# Sensor_Board.net
KiCad netlist of a schematic drawn in Altium Designer
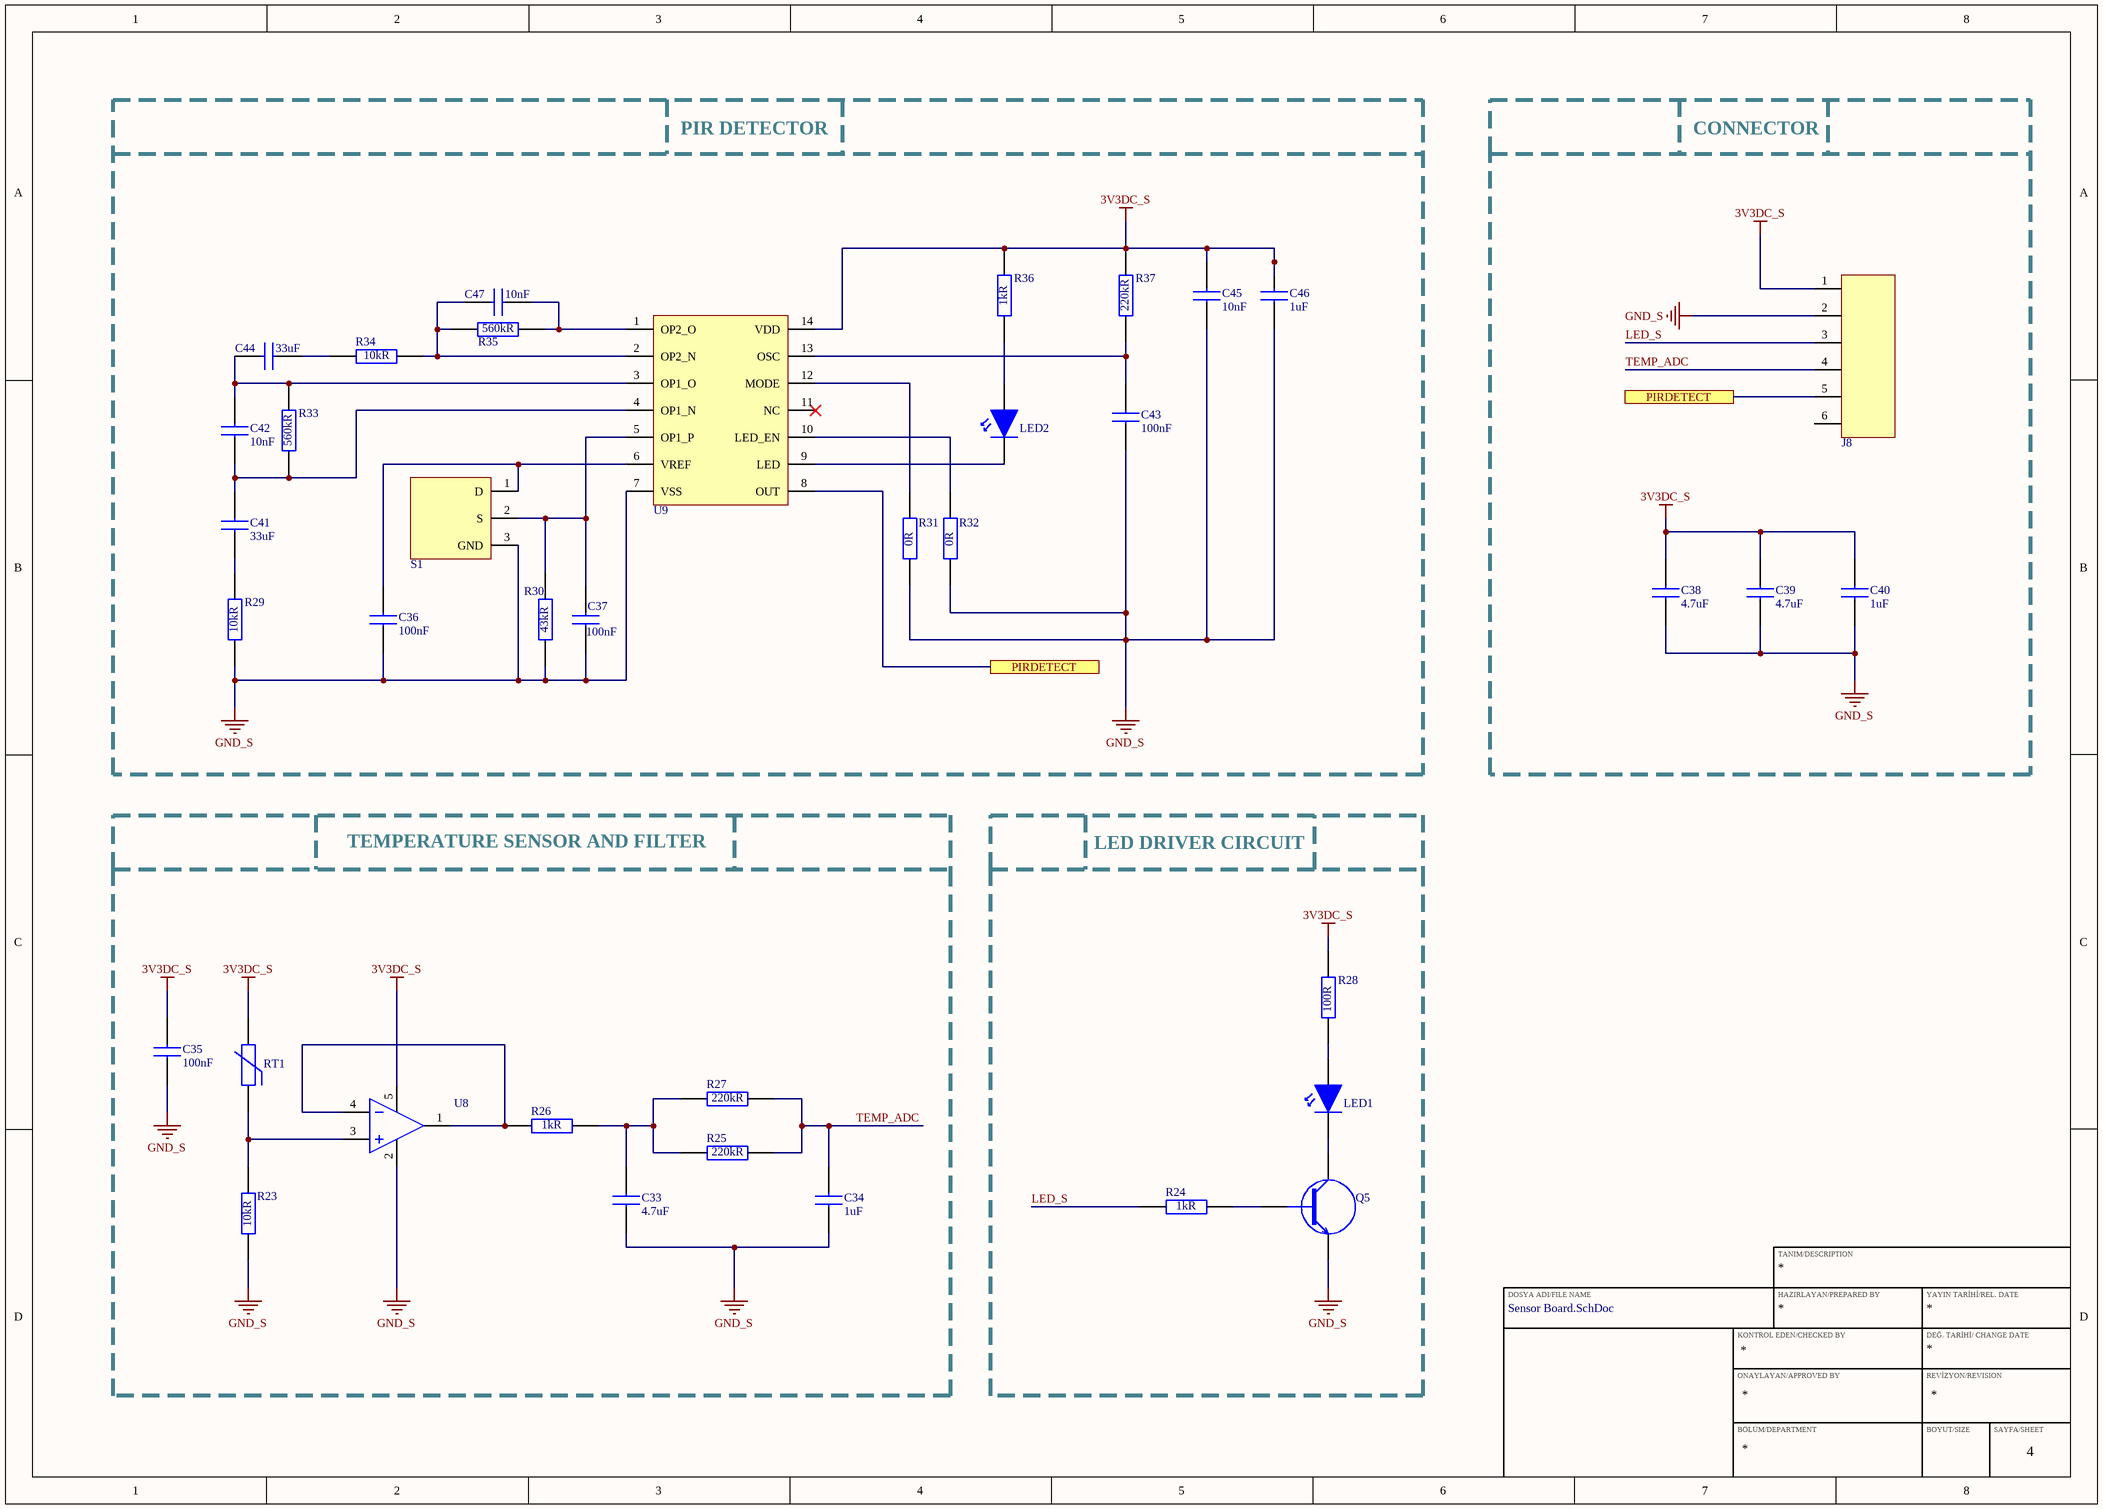
[diagram p0: Sensor Board.SchDoc]

(export (version "E")
  (design (tool "Eeschema 10.0.6"))
  (components
    (comp (ref "C33")
      (value "CL21A475KAQNNNE")
      (footprint "CAP_0805")
      (description "¦CAP CER 4.7UF %10 0805 SMD X5R")
      (fields
        (field (name "MANUFACTURER") "Samsung")
        (field (name "TOLERANCE") "10%")
        (field (name "CAPACITANCE") "4.7uF")
        (field (name "DESIGNED BY") "ADAK")
      )
      (libsource (lib "Udemy_ADAK_Library1") (part "CAP CER 4.7uF 0805"))
    )
    (comp (ref "C34")
      (value "CL21B105KBFNNNE")
      (footprint "CAP_0805")
      (description "¦CAP CER 1UF %10 0805 SMD X7R")
      (fields
        (field (name "MANUFACTURER") "Samsung")
        (field (name "TOLERANCE") "10%")
        (field (name "CAPACITANCE") "1uF")
        (field (name "DESIGNED BY") "ADAK")
      )
      (libsource (lib "Udemy_ADAK_Library1") (part "CAP CER 1uF 0805"))
    )
    (comp (ref "C35")
      (value "C0603C104K4RAC7867")
      (footprint "CAP_0603")
      (description "¦CAP CER 100nF (0.1UF) %10 0603 SMD")
      (fields
        (field (name "MANUFACTURER") "KEMET")
        (field (name "MANUFACTURER PART NUMBER") "C0603C104K4RACTU")
        (field (name "CAPACITANCE") "100nF")
        (field (name "DESIGNED BY") "ADAK")
      )
      (libsource (lib "Udemy_ADAK_Library1") (part "CAP CER 100nF 0603"))
    )
    (comp (ref "C36")
      (value "CL21B104KBCNNNC")
      (footprint "CAP_0805")
      (description "¦CAP CER 0.1UF (100nF) %10 0805 SMD X7R")
      (fields
        (field (name "MANUFACTURER") "Samsung")
        (field (name "TOLERANCE") "10%")
        (field (name "CAPACITANCE") "100nF")
        (field (name "DESIGNED BY") "ADAK")
      )
      (libsource (lib "Udemy_ADAK_Library1") (part "CAP CER 100nF 0805"))
    )
    (comp (ref "C37")
      (value "CL21B104KBCNNNC")
      (footprint "CAP_0805")
      (description "¦CAP CER 0.1UF (100nF) %10 0805 SMD X7R")
      (fields
        (field (name "MANUFACTURER") "Samsung")
        (field (name "TOLERANCE") "10%")
        (field (name "CAPACITANCE") "100nF")
        (field (name "DESIGNED BY") "ADAK")
      )
      (libsource (lib "Udemy_ADAK_Library1") (part "CAP CER 100nF 0805"))
    )
    (comp (ref "C38")
      (value "CL21A475KAQNNNE")
      (footprint "CAP_0805")
      (description "¦CAP CER 4.7UF %10 0805 SMD X5R")
      (fields
        (field (name "MANUFACTURER") "Samsung")
        (field (name "TOLERANCE") "10%")
        (field (name "CAPACITANCE") "4.7uF")
        (field (name "DESIGNED BY") "ADAK")
      )
      (libsource (lib "Udemy_ADAK_Library1") (part "CAP CER 4.7uF 0805"))
    )
    (comp (ref "C39")
      (value "CL21A475KAQNNNE")
      (footprint "CAP_0805")
      (description "¦CAP CER 4.7UF %10 0805 SMD X5R")
      (fields
        (field (name "MANUFACTURER") "Samsung")
        (field (name "TOLERANCE") "10%")
        (field (name "CAPACITANCE") "4.7uF")
        (field (name "DESIGNED BY") "ADAK")
      )
      (libsource (lib "Udemy_ADAK_Library1") (part "CAP CER 4.7uF 0805"))
    )
    (comp (ref "C40")
      (value "CL21B105KBFNNNE")
      (footprint "CAP_0805")
      (description "¦CAP CER 1UF %10 0805 SMD X7R")
      (fields
        (field (name "MANUFACTURER") "Samsung")
        (field (name "TOLERANCE") "10%")
        (field (name "CAPACITANCE") "1uF")
        (field (name "DESIGNED BY") "ADAK")
      )
      (libsource (lib "Udemy_ADAK_Library1") (part "CAP CER 1uF 0805"))
    )
    (comp (ref "C41")
      (value "C2012X5R1A336M125AC")
      (footprint "CAP_0805")
      (description "¦CAP CER 33UF %20 0805 X5R 10V")
      (fields
        (field (name "MANUFACTURER") "TDK")
        (field (name "TOLERANCE") "20%")
        (field (name "CAPACITANCE") "33uF")
        (field (name "DESIGNED BY") "ADAK")
      )
      (libsource (lib "Udemy_ADAK_Library1") (part "CAP CER 33uF 0805"))
    )
    (comp (ref "C42")
      (value "0603B103K160CT")
      (footprint "CAP_0603")
      (description "¦CAP CER 10nF %10 0603 SMD X7R")
      (fields
        (field (name "MANUFACTURER") "Walsin Technologies")
        (field (name "TOLERANCE") "10%")
        (field (name "CAPACITANCE") "10nF")
        (field (name "DESIGNED BY") "ADAK")
      )
      (libsource (lib "Udemy_ADAK_Library1") (part "CAP CER 10nF 0603"))
    )
    (comp (ref "C43")
      (value "CL21B104KBCNNNC")
      (footprint "CAP_0805")
      (description "¦CAP CER 0.1UF (100nF) %10 0805 SMD X7R")
      (fields
        (field (name "MANUFACTURER") "Samsung")
        (field (name "TOLERANCE") "10%")
        (field (name "CAPACITANCE") "100nF")
        (field (name "DESIGNED BY") "ADAK")
      )
      (libsource (lib "Udemy_ADAK_Library1") (part "CAP CER 100nF 0805"))
    )
    (comp (ref "C44")
      (value "C2012X5R1A336M125AC")
      (footprint "CAP_0805")
      (description "¦CAP CER 33UF %20 0805 X5R 10V")
      (fields
        (field (name "MANUFACTURER") "TDK")
        (field (name "TOLERANCE") "20%")
        (field (name "CAPACITANCE") "33uF")
        (field (name "DESIGNED BY") "ADAK")
      )
      (libsource (lib "Udemy_ADAK_Library1") (part "CAP CER 33uF 0805"))
    )
    (comp (ref "C45")
      (value "0603B103K160CT")
      (footprint "CAP_0603")
      (description "¦CAP CER 10nF %10 0603 SMD X7R")
      (fields
        (field (name "MANUFACTURER") "Walsin Technologies")
        (field (name "TOLERANCE") "10%")
        (field (name "CAPACITANCE") "10nF")
        (field (name "DESIGNED BY") "ADAK")
      )
      (libsource (lib "Udemy_ADAK_Library1") (part "CAP CER 10nF 0603"))
    )
    (comp (ref "C46")
      (value "CL21B105KBFNNNE")
      (footprint "CAP_0805")
      (description "¦CAP CER 1UF %10 0805 SMD X7R")
      (fields
        (field (name "MANUFACTURER") "Samsung")
        (field (name "TOLERANCE") "10%")
        (field (name "CAPACITANCE") "1uF")
        (field (name "DESIGNED BY") "ADAK")
      )
      (libsource (lib "Udemy_ADAK_Library1") (part "CAP CER 1uF 0805"))
    )
    (comp (ref "C47")
      (value "0603B103K160CT")
      (footprint "CAP_0603")
      (description "¦CAP CER 10nF %10 0603 SMD X7R")
      (fields
        (field (name "MANUFACTURER") "Walsin Technologies")
        (field (name "TOLERANCE") "10%")
        (field (name "CAPACITANCE") "10nF")
        (field (name "DESIGNED BY") "ADAK")
      )
      (libsource (lib "Udemy_ADAK_Library1") (part "CAP CER 10nF 0603"))
    )
    (comp (ref "J8")
      (value "64800611622")
      (footprint "64800611622")
      (description "¦Connector (1.50mm) 6 Pin Header Through Hole")
      (fields (field (name "MANUFACTURER") "Wurth Electronics") (field (name "DESIGNED BY") "ADAK"))
      (libsource (lib "Udemy_ADAK_Library1") (part "64800611622_CONN_6P"))
    )
    (comp (ref "LED1")
      (value "150080SS75000")
      (footprint "LED_RED_0805")
      (description "¦LED RED CLEAR 0805 SMD")
      (fields (field (name "MANUFACTURER") "Wurth Electronics") (field (name "DESIGNED BY") "ADAK"))
      (libsource (lib "Udemy_ADAK_Library1") (part "LED RED 0805"))
    )
    (comp (ref "LED2")
      (value "150080GS75000")
      (footprint "LED_GREEN_0805")
      (description "¦LED GREEN CLEAR 0805 SMD")
      (fields (field (name "MANUFACTURER") "Wurth Electronics") (field (name "DESIGNED BY") "ADAK"))
      (libsource (lib "Udemy_ADAK_Library1") (part "LED GREEN 0805"))
    )
    (comp (ref "Q5")
      (value "MMBT3904-7-F")
      (footprint "SOT-23F")
      (description "¦Bipolar (BJT) Transistor NPN 40 V 200 mA 300MHz 300 mW Surface Mount SOT-23-3")
      (fields (field (name "MANUFACTURER") "Diodes Zetex") (field (name "DESIGNED BY") "ADAK"))
      (libsource (lib "Udemy_ADAK_Library1") (part "MMBT3904-7-F"))
    )
    (comp (ref "R23")
      (value "RC0603FR-0710KL")
      (footprint "RES_0603")
      (description "¦RES 10KΩ 1% 0603 SMD")
      (fields
        (field (name "MANUFACTURER") "Yageo")
        (field (name "TOLERANCE") "1%")
        (field (name "RESISTANCE") "10kR")
        (field (name "DESIGNED BY") "ADAK")
      )
      (libsource (lib "Udemy_ADAK_Library1") (part "RES 10K OHM 0603"))
    )
    (comp (ref "R24")
      (value "RC0603FR-071KL")
      (footprint "RES_0603")
      (description "¦RES 1KΩ 1% 0603 SMD")
      (fields
        (field (name "MANUFACTURER") "Yageo")
        (field (name "TOLERANCE") "1%")
        (field (name "RESISTANCE") "1kR")
        (field (name "DESIGNED BY") "ADAK")
      )
      (libsource (lib "Udemy_ADAK_Library1") (part "RES 1K OHM 0603"))
    )
    (comp (ref "R25")
      (value "RC0603JR-07220KL")
      (footprint "RES_0603")
      (description "¦RES 220KΩ 5% 0603 SMD")
      (fields
        (field (name "MANUFACTURER") "Yageo")
        (field (name "TOLERANCE") "5%")
        (field (name "RESISTANCE") "220kR")
        (field (name "DESIGNED BY") "ADAK")
      )
      (libsource (lib "Udemy_ADAK_Library1") (part "RES 220K OHM 0603"))
    )
    (comp (ref "R26")
      (value "RC0603FR-071KL")
      (footprint "RES_0603")
      (description "¦RES 1KΩ 1% 0603 SMD")
      (fields
        (field (name "MANUFACTURER") "Yageo")
        (field (name "TOLERANCE") "1%")
        (field (name "RESISTANCE") "1kR")
        (field (name "DESIGNED BY") "ADAK")
      )
      (libsource (lib "Udemy_ADAK_Library1") (part "RES 1K OHM 0603"))
    )
    (comp (ref "R27")
      (value "RC0603JR-07220KL")
      (footprint "RES_0603")
      (description "¦RES 220KΩ 5% 0603 SMD")
      (fields
        (field (name "MANUFACTURER") "Yageo")
        (field (name "TOLERANCE") "5%")
        (field (name "RESISTANCE") "220kR")
        (field (name "DESIGNED BY") "ADAK")
      )
      (libsource (lib "Udemy_ADAK_Library1") (part "RES 220K OHM 0603"))
    )
    (comp (ref "R28")
      (value "RC0603JR-13100RL")
      (footprint "RES_0603")
      (description "¦RES 100Ω 5% 0603 SMD")
      (fields
        (field (name "MANUFACTURER") "Yageo")
        (field (name "TOLERANCE") "5%")
        (field (name "RESISTANCE") "100R")
        (field (name "DESIGNED BY") "ADAK")
      )
      (libsource (lib "Udemy_ADAK_Library1") (part "RES 100 OHM 0603"))
    )
    (comp (ref "R29")
      (value "RC0603FR-0710KL")
      (footprint "RES_0603")
      (description "¦RES 10KΩ 1% 0603 SMD")
      (fields
        (field (name "MANUFACTURER") "Yageo")
        (field (name "TOLERANCE") "1%")
        (field (name "RESISTANCE") "10kR")
        (field (name "DESIGNED BY") "ADAK")
      )
      (libsource (lib "Udemy_ADAK_Library1") (part "RES 10K OHM 0603"))
    )
    (comp (ref "R30")
      (value "RC0603FR-0743KL")
      (footprint "RES_0603")
      (description "¦RES 43KΩ 1% 0603 SMD")
      (fields
        (field (name "MANUFACTURER") "Yageo")
        (field (name "TOLERANCE") "1%")
        (field (name "RESISTANCE") "43kR")
        (field (name "DESIGNED BY") "ADAK")
      )
      (libsource (lib "Udemy_ADAK_Library1") (part "RES 43K OHM 0603"))
    )
    (comp (ref "R31")
      (value "RC0603JR-070RL")
      (footprint "RES_0603")
      (description "¦RES 0Ω 0603 SMD JUMPER")
      (fields
        (field (name "MANUFACTURER") "Yageo")
        (field (name "TOLERANCE") "1%")
        (field (name "RESISTANCE") "0R")
        (field (name "DESIGNED BY") "ADAK")
      )
      (libsource (lib "Udemy_ADAK_Library1") (part "RES 0 OHM 0603"))
    )
    (comp (ref "R32")
      (value "RC0603JR-070RL")
      (footprint "RES_0603")
      (description "¦RES 0Ω 0603 SMD JUMPER")
      (fields
        (field (name "MANUFACTURER") "Yageo")
        (field (name "TOLERANCE") "1%")
        (field (name "RESISTANCE") "0R")
        (field (name "DESIGNED BY") "ADAK")
      )
      (libsource (lib "Udemy_ADAK_Library1") (part "RES 0 OHM 0603"))
    )
    (comp (ref "R33")
      (value "RC0603JR-07560KL")
      (footprint "RES_0603")
      (description "¦RES 560KΩ 5% 0603 SMD")
      (fields
        (field (name "MANUFACTURER") "Yageo")
        (field (name "TOLERANCE") "5%")
        (field (name "RESISTANCE") "560kR")
        (field (name "DESIGNED BY") "ADAK")
      )
      (libsource (lib "Udemy_ADAK_Library1") (part "RES 560K OHM 0603"))
    )
    (comp (ref "R34")
      (value "RC0603FR-0710KL")
      (footprint "RES_0603")
      (description "¦RES 10KΩ 1% 0603 SMD")
      (fields
        (field (name "MANUFACTURER") "Yageo")
        (field (name "TOLERANCE") "1%")
        (field (name "RESISTANCE") "10kR")
        (field (name "DESIGNED BY") "ADAK")
      )
      (libsource (lib "Udemy_ADAK_Library1") (part "RES 10K OHM 0603"))
    )
    (comp (ref "R35")
      (value "RC0603JR-07560KL")
      (footprint "RES_0603")
      (description "¦RES 560KΩ 5% 0603 SMD")
      (fields
        (field (name "MANUFACTURER") "Yageo")
        (field (name "TOLERANCE") "5%")
        (field (name "RESISTANCE") "560kR")
        (field (name "DESIGNED BY") "ADAK")
      )
      (libsource (lib "Udemy_ADAK_Library1") (part "RES 560K OHM 0603"))
    )
    (comp (ref "R36")
      (value "RC0603FR-071KL")
      (footprint "RES_0603")
      (description "¦RES 1KΩ 1% 0603 SMD")
      (fields
        (field (name "MANUFACTURER") "Yageo")
        (field (name "TOLERANCE") "1%")
        (field (name "RESISTANCE") "1kR")
        (field (name "DESIGNED BY") "ADAK")
      )
      (libsource (lib "Udemy_ADAK_Library1") (part "RES 1K OHM 0603"))
    )
    (comp (ref "R37")
      (value "RC0603JR-07220KL")
      (footprint "RES_0603")
      (description "¦RES 220KΩ 5% 0603 SMD")
      (fields
        (field (name "MANUFACTURER") "Yageo")
        (field (name "TOLERANCE") "5%")
        (field (name "RESISTANCE") "220kR")
        (field (name "DESIGNED BY") "ADAK")
      )
      (libsource (lib "Udemy_ADAK_Library1") (part "RES 220K OHM 0603"))
    )
    (comp (ref "RT1")
      (value "TFPT1206L1002FM")
      (footprint "RES_1206")
      (description "¦Thermistor PTC 10K Ohm 1%  1206 Surface Mount")
      (fields
        (field (name "MANUFACTURER") "Vishay Dale")
        (field (name "TOLERANCE") "1%")
        (field (name "DESIGNED BY") "ADAK")
      )
      (libsource (lib "Udemy_ADAK_Library1") (part "TFPT1206L1002FM"))
    )
    (comp (ref "S1")
      (value "LHI 878/3902")
      (footprint "LHI 878")
      (description "¦Sensor PIR (Passive Infrared) TO-205AA, TO-5-3 Metal Can")
      (fields (field (name "MANUFACTURER") "Excelitas") (field (name "DESIGNED BY") "ADAK"))
      (libsource (lib "Udemy_ADAK_Library1") (part "LHI 878/3902"))
    )
    (comp (ref "U8")
      (value "OPA314AIDBVT")
      (footprint "SOT23-5")
      (description "¦Operational Amplifiers - Op Amps 3MHz,RRIO,1.8V CMOS Op Amp")
      (fields (field (name "MANUFACTURER") "Texas Instruments") (field (name "DESIGNED BY") "ADAK"))
      (libsource (lib "Udemy_ADAK_Library1") (part "OPA314"))
    )
    (comp (ref "U9")
      (value "NCS36000DRG")
      (footprint "SOIC-14")
      (description "¦PIR Detector Controller 14-SOIC Low Noise Amplifiers")
      (fields (field (name "MANUFACTURER") "ON Semiconductor") (field (name "DESIGNED BY") "ADAK"))
      (libsource (lib "Udemy_ADAK_Library1") (part "NCS36000DRG"))
    )
  )
  (nets
    (net (code "1") (name "/LED_S") (class "Default")
      (node (ref "J8") (pin "3") (pinfunction "3_3") (pintype "passive"))
      (node (ref "R24") (pin "1") (pinfunction "1_1") (pintype "passive"))
    )
    (net (code "2") (name "/PIRDETECT") (class "Default")
      (node (ref "J8") (pin "5") (pinfunction "5_5") (pintype "passive"))
      (node (ref "U9") (pin "8") (pinfunction "OUT_8") (pintype "passive"))
    )
    (net (code "3") (name "/TEMP_ADC") (class "Default")
      (node (ref "C34") (pin "2") (pinfunction "2_2") (pintype "passive"))
      (node (ref "J8") (pin "4") (pinfunction "4_4") (pintype "passive"))
      (node (ref "R25") (pin "2") (pinfunction "2_2") (pintype "passive"))
      (node (ref "R27") (pin "2") (pinfunction "2_2") (pintype "passive"))
    )
    (net (code "4") (name "3V3DC_S") (class "Default")
      (node (ref "C35") (pin "2") (pinfunction "2_2") (pintype "passive"))
      (node (ref "C38") (pin "2") (pinfunction "2_2") (pintype "passive"))
      (node (ref "C39") (pin "2") (pinfunction "2_2") (pintype "passive"))
      (node (ref "C40") (pin "2") (pinfunction "2_2") (pintype "passive"))
      (node (ref "C45") (pin "2") (pinfunction "2_2") (pintype "passive"))
      (node (ref "C46") (pin "2") (pinfunction "2_2") (pintype "passive"))
      (node (ref "J8") (pin "1") (pinfunction "1_1") (pintype "passive"))
      (node (ref "R28") (pin "2") (pinfunction "2_2") (pintype "passive"))
      (node (ref "R36") (pin "2") (pinfunction "2_2") (pintype "passive"))
      (node (ref "R37") (pin "2") (pinfunction "2_2") (pintype "passive"))
      (node (ref "RT1") (pin "2") (pinfunction "2_2") (pintype "passive"))
      (node (ref "U8") (pin "5") (pinfunction "5_5") (pintype "passive"))
      (node (ref "U9") (pin "14") (pinfunction "VDD_14") (pintype "passive"))
    )
    (net (code "5") (name "GND_S") (class "Default")
      (node (ref "C33") (pin "1") (pinfunction "1_1") (pintype "passive"))
      (node (ref "C34") (pin "1") (pinfunction "1_1") (pintype "passive"))
      (node (ref "C35") (pin "1") (pinfunction "1_1") (pintype "passive"))
      (node (ref "C36") (pin "1") (pinfunction "1_1") (pintype "passive"))
      (node (ref "C37") (pin "2") (pinfunction "2_2") (pintype "passive"))
      (node (ref "C38") (pin "1") (pinfunction "1_1") (pintype "passive"))
      (node (ref "C39") (pin "1") (pinfunction "1_1") (pintype "passive"))
      (node (ref "C40") (pin "1") (pinfunction "1_1") (pintype "passive"))
      (node (ref "C43") (pin "2") (pinfunction "2_2") (pintype "passive"))
      (node (ref "C45") (pin "1") (pinfunction "1_1") (pintype "passive"))
      (node (ref "C46") (pin "1") (pinfunction "1_1") (pintype "passive"))
      (node (ref "J8") (pin "2") (pinfunction "2_2") (pintype "passive"))
      (node (ref "Q5") (pin "2") (pinfunction "E_2") (pintype "passive"))
      (node (ref "R23") (pin "1") (pinfunction "1_1") (pintype "passive"))
      (node (ref "R29") (pin "2") (pinfunction "2_2") (pintype "passive"))
      (node (ref "R30") (pin "1") (pinfunction "1_1") (pintype "passive"))
      (node (ref "R31") (pin "1") (pinfunction "1_1") (pintype "passive"))
      (node (ref "R32") (pin "1") (pinfunction "1_1") (pintype "passive"))
      (node (ref "S1") (pin "3") (pinfunction "GND_3") (pintype "passive"))
      (node (ref "U8") (pin "2") (pinfunction "2_2") (pintype "passive"))
      (node (ref "U9") (pin "7") (pinfunction "VSS_7") (pintype "passive"))
    )
    (net (code "6") (name "Net-(C33-Pad2)") (class "Default")
      (node (ref "C33") (pin "2") (pinfunction "2_2") (pintype "passive"))
      (node (ref "R25") (pin "1") (pinfunction "1_1") (pintype "passive"))
      (node (ref "R26") (pin "2") (pinfunction "2_2") (pintype "passive"))
      (node (ref "R27") (pin "1") (pinfunction "1_1") (pintype "passive"))
    )
    (net (code "7") (name "Net-(C41-Pad2)") (class "Default")
      (node (ref "C41") (pin "2") (pinfunction "2_2") (pintype "passive"))
      (node (ref "R29") (pin "1") (pinfunction "1_1") (pintype "passive"))
    )
    (net (code "8") (name "Net-(C44-Pad2)") (class "Default")
      (node (ref "C44") (pin "2") (pinfunction "2_2") (pintype "passive"))
      (node (ref "R34") (pin "1") (pinfunction "1_1") (pintype "passive"))
    )
    (net (code "9") (name "Net-(LED1-Pad2)") (class "Default")
      (node (ref "LED1") (pin "2") (pinfunction "2_2") (pintype "passive"))
      (node (ref "R28") (pin "1") (pinfunction "1_1") (pintype "passive"))
    )
    (net (code "10") (name "Net-(LED2-Pad2)") (class "Default")
      (node (ref "LED2") (pin "2") (pinfunction "2_2") (pintype "passive"))
      (node (ref "R36") (pin "1") (pinfunction "1_1") (pintype "passive"))
    )
    (net (code "11") (name "Net-(Q5-B)") (class "Default")
      (node (ref "Q5") (pin "1") (pinfunction "B_1") (pintype "passive"))
      (node (ref "R24") (pin "2") (pinfunction "2_2") (pintype "passive"))
    )
    (net (code "12") (name "Net-(Q5-C)") (class "Default")
      (node (ref "LED1") (pin "1") (pinfunction "1_1") (pintype "passive"))
      (node (ref "Q5") (pin "3") (pinfunction "C_3") (pintype "passive"))
    )
    (net (code "13") (name "Net-(R23-Pad2)") (class "Default")
      (node (ref "R23") (pin "2") (pinfunction "2_2") (pintype "passive"))
      (node (ref "RT1") (pin "1") (pinfunction "1_1") (pintype "passive"))
      (node (ref "U8") (pin "3") (pinfunction "3_3") (pintype "passive"))
    )
    (net (code "14") (name "Net-(R26-Pad1)") (class "Default")
      (node (ref "R26") (pin "1") (pinfunction "1_1") (pintype "passive"))
      (node (ref "U8") (pin "1") (pinfunction "1_1") (pintype "passive"))
      (node (ref "U8") (pin "4") (pinfunction "4_4") (pintype "passive"))
    )
    (net (code "15") (name "Net-(S1-D)") (class "Default")
      (node (ref "C36") (pin "2") (pinfunction "2_2") (pintype "passive"))
      (node (ref "S1") (pin "1") (pinfunction "D_1") (pintype "passive"))
      (node (ref "U9") (pin "6") (pinfunction "VREF_6") (pintype "passive"))
    )
    (net (code "16") (name "Net-(S1-S)") (class "Default")
      (node (ref "C37") (pin "1") (pinfunction "1_1") (pintype "passive"))
      (node (ref "R30") (pin "2") (pinfunction "2_2") (pintype "passive"))
      (node (ref "S1") (pin "2") (pinfunction "S_2") (pintype "passive"))
      (node (ref "U9") (pin "5") (pinfunction "OP1_P_5") (pintype "passive"))
    )
    (net (code "17") (name "Net-(U9-LED)") (class "Default")
      (node (ref "LED2") (pin "1") (pinfunction "1_1") (pintype "passive"))
      (node (ref "U9") (pin "9") (pinfunction "LED_9") (pintype "passive"))
    )
    (net (code "18") (name "Net-(U9-LED_EN)") (class "Default")
      (node (ref "R32") (pin "2") (pinfunction "2_2") (pintype "passive"))
      (node (ref "U9") (pin "10") (pinfunction "LED_EN_10") (pintype "passive"))
    )
    (net (code "19") (name "Net-(U9-MODE)") (class "Default")
      (node (ref "R31") (pin "2") (pinfunction "2_2") (pintype "passive"))
      (node (ref "U9") (pin "12") (pinfunction "MODE_12") (pintype "passive"))
    )
    (net (code "20") (name "Net-(U9-OP1_N)") (class "Default")
      (node (ref "C41") (pin "1") (pinfunction "1_1") (pintype "passive"))
      (node (ref "C42") (pin "2") (pinfunction "2_2") (pintype "passive"))
      (node (ref "R33") (pin "2") (pinfunction "2_2") (pintype "passive"))
      (node (ref "U9") (pin "4") (pinfunction "OP1_N_4") (pintype "passive"))
    )
    (net (code "21") (name "Net-(U9-OP1_O)") (class "Default")
      (node (ref "C42") (pin "1") (pinfunction "1_1") (pintype "passive"))
      (node (ref "C44") (pin "1") (pinfunction "1_1") (pintype "passive"))
      (node (ref "R33") (pin "1") (pinfunction "1_1") (pintype "passive"))
      (node (ref "U9") (pin "3") (pinfunction "OP1_O_3") (pintype "passive"))
    )
    (net (code "22") (name "Net-(U9-OP2_N)") (class "Default")
      (node (ref "C47") (pin "1") (pinfunction "1_1") (pintype "passive"))
      (node (ref "R34") (pin "2") (pinfunction "2_2") (pintype "passive"))
      (node (ref "R35") (pin "1") (pinfunction "1_1") (pintype "passive"))
      (node (ref "U9") (pin "2") (pinfunction "OP2_N_2") (pintype "passive"))
    )
    (net (code "23") (name "Net-(U9-OP2_O)") (class "Default")
      (node (ref "C47") (pin "2") (pinfunction "2_2") (pintype "passive"))
      (node (ref "R35") (pin "2") (pinfunction "2_2") (pintype "passive"))
      (node (ref "U9") (pin "1") (pinfunction "OP2_O_1") (pintype "passive"))
    )
    (net (code "24") (name "Net-(U9-OSC)") (class "Default")
      (node (ref "C43") (pin "1") (pinfunction "1_1") (pintype "passive"))
      (node (ref "R37") (pin "1") (pinfunction "1_1") (pintype "passive"))
      (node (ref "U9") (pin "13") (pinfunction "OSC_13") (pintype "passive"))
    )
    (net (code "25") (name "unconnected-(J8-Pad6)") (class "Default")
      (node (ref "J8") (pin "6") (pinfunction "6_6") (pintype "passive"))
    )
    (net (code "26") (name "unconnected-(U9-NC-Pad11)") (class "Default")
      (node (ref "U9") (pin "11") (pinfunction "NC_11") (pintype "passive+no_connect"))
    )
  )
)
